# DAC.net
KiCad netlist of a schematic drawn in Altium Designer
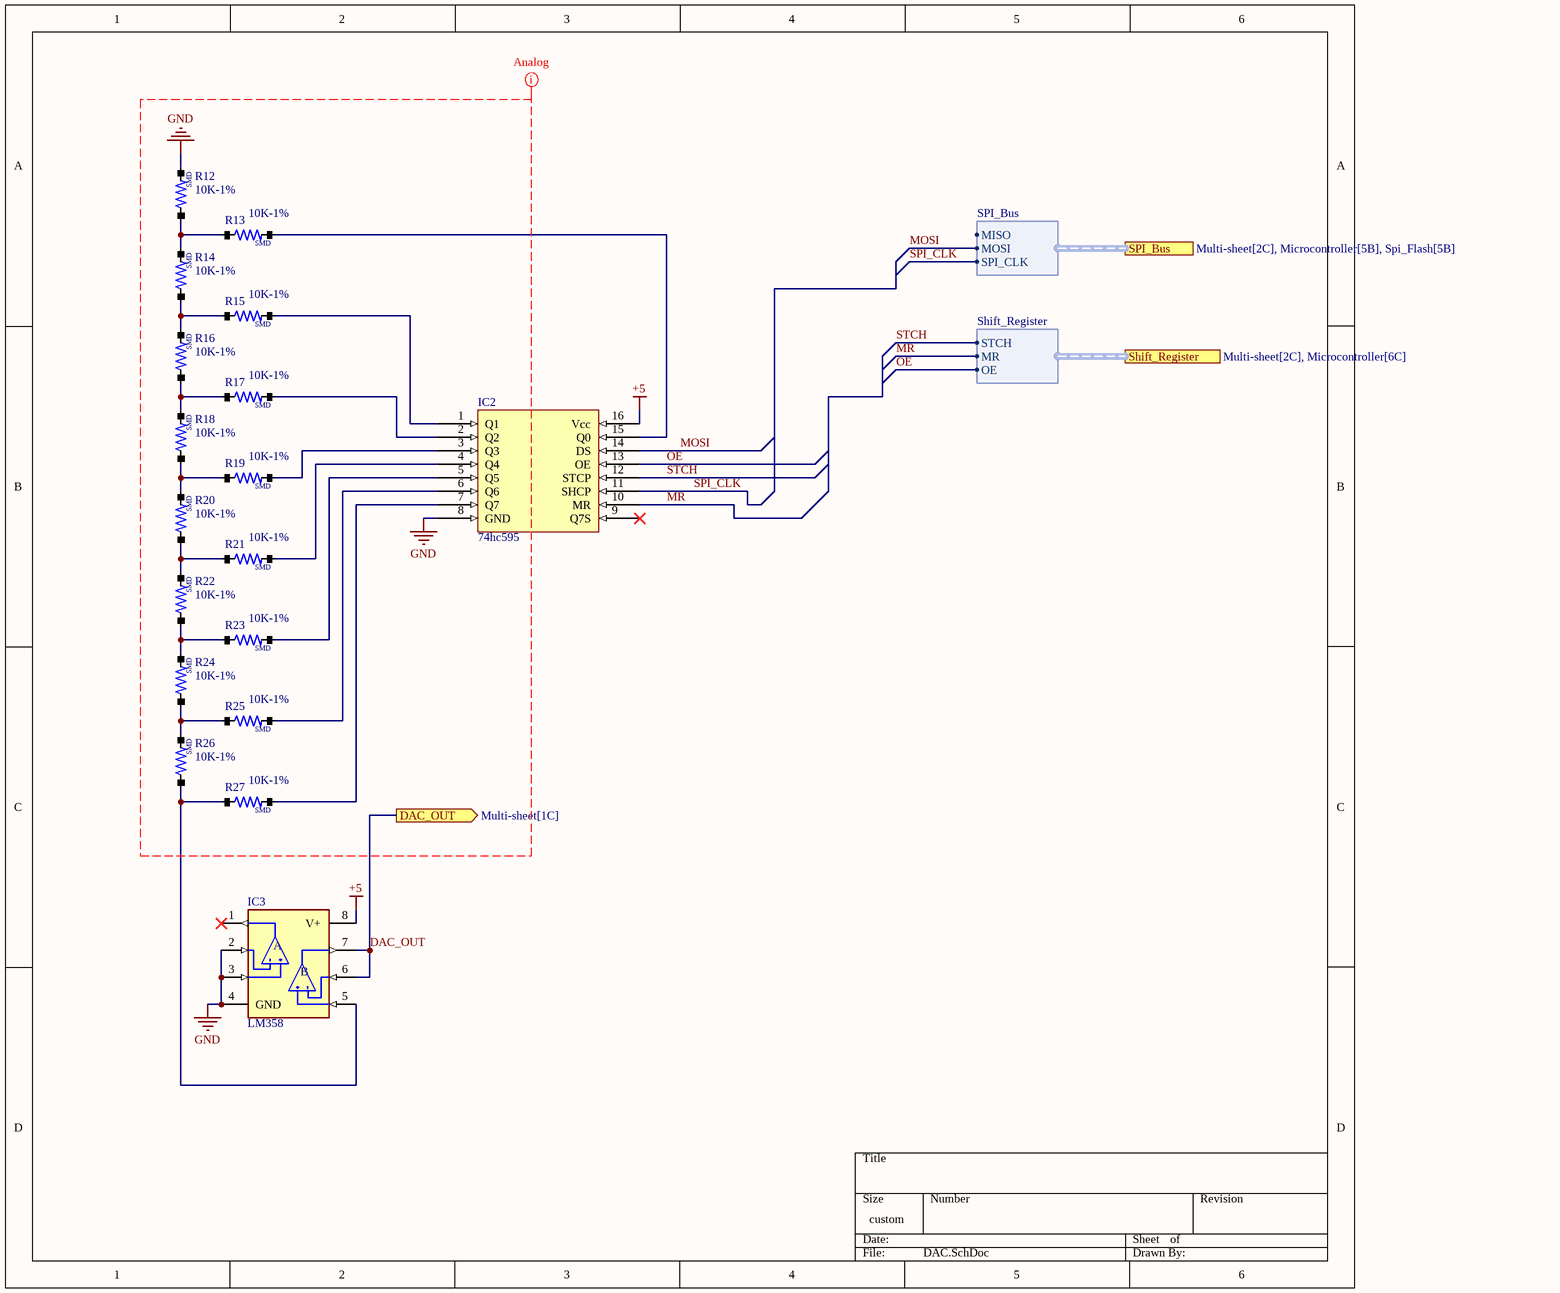
[diagram p0: DAC.SchDoc]

(export (version "E")
  (design (tool "Eeschema 10.0.6"))
  (components
    (comp (ref "IC2") (value "74hc595") (footprint "SOP16") (libsource (lib "kave-eng-pro") (part "74hc595")))
    (comp (ref "IC3") (value "LM358") (footprint "SOP-8") (libsource (lib "kave-eng-pro") (part "LM358")))
    (comp (ref "R12") (value "10K-1%") (footprint "RES/0603") (libsource (lib "") (part "RES/SMD_1")))
    (comp (ref "R13")
      (value "10K-1%")
      (footprint "RES/0603")
      (libsource (lib "kave-eng-pro") (part "RES/SMD"))
    )
    (comp (ref "R14") (value "10K-1%") (footprint "RES/0603") (libsource (lib "") (part "RES/SMD_1")))
    (comp (ref "R15")
      (value "10K-1%")
      (footprint "RES/0603")
      (libsource (lib "kave-eng-pro") (part "RES/SMD"))
    )
    (comp (ref "R16") (value "10K-1%") (footprint "RES/0603") (libsource (lib "") (part "RES/SMD_1")))
    (comp (ref "R17")
      (value "10K-1%")
      (footprint "RES/0603")
      (libsource (lib "kave-eng-pro") (part "RES/SMD"))
    )
    (comp (ref "R18") (value "10K-1%") (footprint "RES/0603") (libsource (lib "") (part "RES/SMD_1")))
    (comp (ref "R19")
      (value "10K-1%")
      (footprint "RES/0603")
      (libsource (lib "kave-eng-pro") (part "RES/SMD"))
    )
    (comp (ref "R20") (value "10K-1%") (footprint "RES/0603") (libsource (lib "") (part "RES/SMD_1")))
    (comp (ref "R21")
      (value "10K-1%")
      (footprint "RES/0603")
      (libsource (lib "kave-eng-pro") (part "RES/SMD"))
    )
    (comp (ref "R22") (value "10K-1%") (footprint "RES/0603") (libsource (lib "") (part "RES/SMD_1")))
    (comp (ref "R23")
      (value "10K-1%")
      (footprint "RES/0603")
      (libsource (lib "kave-eng-pro") (part "RES/SMD"))
    )
    (comp (ref "R24") (value "10K-1%") (footprint "RES/0603") (libsource (lib "") (part "RES/SMD_1")))
    (comp (ref "R25")
      (value "10K-1%")
      (footprint "RES/0603")
      (libsource (lib "kave-eng-pro") (part "RES/SMD"))
    )
    (comp (ref "R26") (value "10K-1%") (footprint "RES/0603") (libsource (lib "") (part "RES/SMD_1")))
    (comp (ref "R27")
      (value "10K-1%")
      (footprint "RES/0603")
      (libsource (lib "kave-eng-pro") (part "RES/SMD"))
    )
  )
  (nets
    (net (code "3") (name "+5") (class "Default")
      (node (ref "IC2") (pin "16") (pinfunction "Vcc_16") (pintype "input"))
      (node (ref "IC3") (pin "8") (pinfunction "V+_8") (pintype "power_in"))
    )
    (net (code "4") (name "/DAC_OUT") (class "Default")
      (node (ref "IC3") (pin "6") (pinfunction "-INB_6") (pintype "input"))
      (node (ref "IC3") (pin "7") (pinfunction "OUTB_7") (pintype "output"))
    )
    (net (code "5") (name "/MOSI") (class "Default")
      (node (ref "IC2") (pin "14") (pinfunction "DS_14") (pintype "input"))
    )
    (net (code "6") (name "/MR") (class "Default")
      (node (ref "IC2") (pin "10") (pinfunction "MR_10") (pintype "input"))
    )
    (net (code "7") (name "/OE") (class "Default")
      (node (ref "IC2") (pin "13") (pinfunction "OE_13") (pintype "input"))
    )
    (net (code "8") (name "/SPI_CLK") (class "Default")
      (node (ref "IC2") (pin "11") (pinfunction "SHCP_11") (pintype "input"))
    )
    (net (code "9") (name "/STCH") (class "Default")
      (node (ref "IC2") (pin "12") (pinfunction "STCP_12") (pintype "input"))
    )
    (net (code "12") (name "GND") (class "Default")
      (node (ref "IC2") (pin "8") (pinfunction "GND_8") (pintype "input"))
      (node (ref "IC3") (pin "2") (pinfunction "-INA_2") (pintype "input"))
      (node (ref "IC3") (pin "3") (pinfunction "+INA_3") (pintype "input"))
      (node (ref "IC3") (pin "4") (pinfunction "GND_4") (pintype "power_in"))
      (node (ref "R12") (pin "2") (pinfunction "2_2") (pintype "passive"))
    )
    (net (code "13") (name "Net-(IC2-Q0)") (class "Default")
      (node (ref "IC2") (pin "15") (pinfunction "Q0_15") (pintype "input"))
      (node (ref "R13") (pin "2") (pinfunction "2_2") (pintype "passive"))
    )
    (net (code "14") (name "Net-(IC2-Q1)") (class "Default")
      (node (ref "IC2") (pin "1") (pinfunction "Q1_1") (pintype "input"))
      (node (ref "R15") (pin "2") (pinfunction "2_2") (pintype "passive"))
    )
    (net (code "15") (name "Net-(IC2-Q2)") (class "Default")
      (node (ref "IC2") (pin "2") (pinfunction "Q2_2") (pintype "input"))
      (node (ref "R17") (pin "2") (pinfunction "2_2") (pintype "passive"))
    )
    (net (code "16") (name "Net-(IC2-Q3)") (class "Default")
      (node (ref "IC2") (pin "3") (pinfunction "Q3_3") (pintype "input"))
      (node (ref "R19") (pin "2") (pinfunction "2_2") (pintype "passive"))
    )
    (net (code "17") (name "Net-(IC2-Q4)") (class "Default")
      (node (ref "IC2") (pin "4") (pinfunction "Q4_4") (pintype "input"))
      (node (ref "R21") (pin "2") (pinfunction "2_2") (pintype "passive"))
    )
    (net (code "18") (name "Net-(IC2-Q5)") (class "Default")
      (node (ref "IC2") (pin "5") (pinfunction "Q5_5") (pintype "input"))
      (node (ref "R23") (pin "2") (pinfunction "2_2") (pintype "passive"))
    )
    (net (code "19") (name "Net-(IC2-Q6)") (class "Default")
      (node (ref "IC2") (pin "6") (pinfunction "Q6_6") (pintype "input"))
      (node (ref "R25") (pin "2") (pinfunction "2_2") (pintype "passive"))
    )
    (net (code "20") (name "Net-(IC2-Q7)") (class "Default")
      (node (ref "IC2") (pin "7") (pinfunction "Q7_7") (pintype "input"))
      (node (ref "R27") (pin "2") (pinfunction "2_2") (pintype "passive"))
    )
    (net (code "21") (name "Net-(IC3-+INB)") (class "Default")
      (node (ref "IC3") (pin "5") (pinfunction "+INB_5") (pintype "input"))
      (node (ref "R26") (pin "1") (pinfunction "1_1") (pintype "passive"))
      (node (ref "R27") (pin "1") (pinfunction "1_1") (pintype "passive"))
    )
    (net (code "22") (name "Net-(R12-Pad1)") (class "Default")
      (node (ref "R12") (pin "1") (pinfunction "1_1") (pintype "passive"))
      (node (ref "R13") (pin "1") (pinfunction "1_1") (pintype "passive"))
      (node (ref "R14") (pin "2") (pinfunction "2_2") (pintype "passive"))
    )
    (net (code "23") (name "Net-(R14-Pad1)") (class "Default")
      (node (ref "R14") (pin "1") (pinfunction "1_1") (pintype "passive"))
      (node (ref "R15") (pin "1") (pinfunction "1_1") (pintype "passive"))
      (node (ref "R16") (pin "2") (pinfunction "2_2") (pintype "passive"))
    )
    (net (code "24") (name "Net-(R16-Pad1)") (class "Default")
      (node (ref "R16") (pin "1") (pinfunction "1_1") (pintype "passive"))
      (node (ref "R17") (pin "1") (pinfunction "1_1") (pintype "passive"))
      (node (ref "R18") (pin "2") (pinfunction "2_2") (pintype "passive"))
    )
    (net (code "25") (name "Net-(R18-Pad1)") (class "Default")
      (node (ref "R18") (pin "1") (pinfunction "1_1") (pintype "passive"))
      (node (ref "R19") (pin "1") (pinfunction "1_1") (pintype "passive"))
      (node (ref "R20") (pin "2") (pinfunction "2_2") (pintype "passive"))
    )
    (net (code "26") (name "Net-(R20-Pad1)") (class "Default")
      (node (ref "R20") (pin "1") (pinfunction "1_1") (pintype "passive"))
      (node (ref "R21") (pin "1") (pinfunction "1_1") (pintype "passive"))
      (node (ref "R22") (pin "2") (pinfunction "2_2") (pintype "passive"))
    )
    (net (code "27") (name "Net-(R22-Pad1)") (class "Default")
      (node (ref "R22") (pin "1") (pinfunction "1_1") (pintype "passive"))
      (node (ref "R23") (pin "1") (pinfunction "1_1") (pintype "passive"))
      (node (ref "R24") (pin "2") (pinfunction "2_2") (pintype "passive"))
    )
    (net (code "28") (name "Net-(R24-Pad1)") (class "Default")
      (node (ref "R24") (pin "1") (pinfunction "1_1") (pintype "passive"))
      (node (ref "R25") (pin "1") (pinfunction "1_1") (pintype "passive"))
      (node (ref "R26") (pin "2") (pinfunction "2_2") (pintype "passive"))
    )
    (net (code "29") (name "unconnected-(IC2-Q7S-Pad9)") (class "Default")
      (node (ref "IC2") (pin "9") (pinfunction "Q7S_9") (pintype "input+no_connect"))
    )
    (net (code "30") (name "unconnected-(IC3-OUTA-Pad1)") (class "Default")
      (node (ref "IC3") (pin "1") (pinfunction "OUTA_1") (pintype "output+no_connect"))
    )
  )
)
